# hexapod.net
KiCad netlist of a schematic drawn in EAGLE
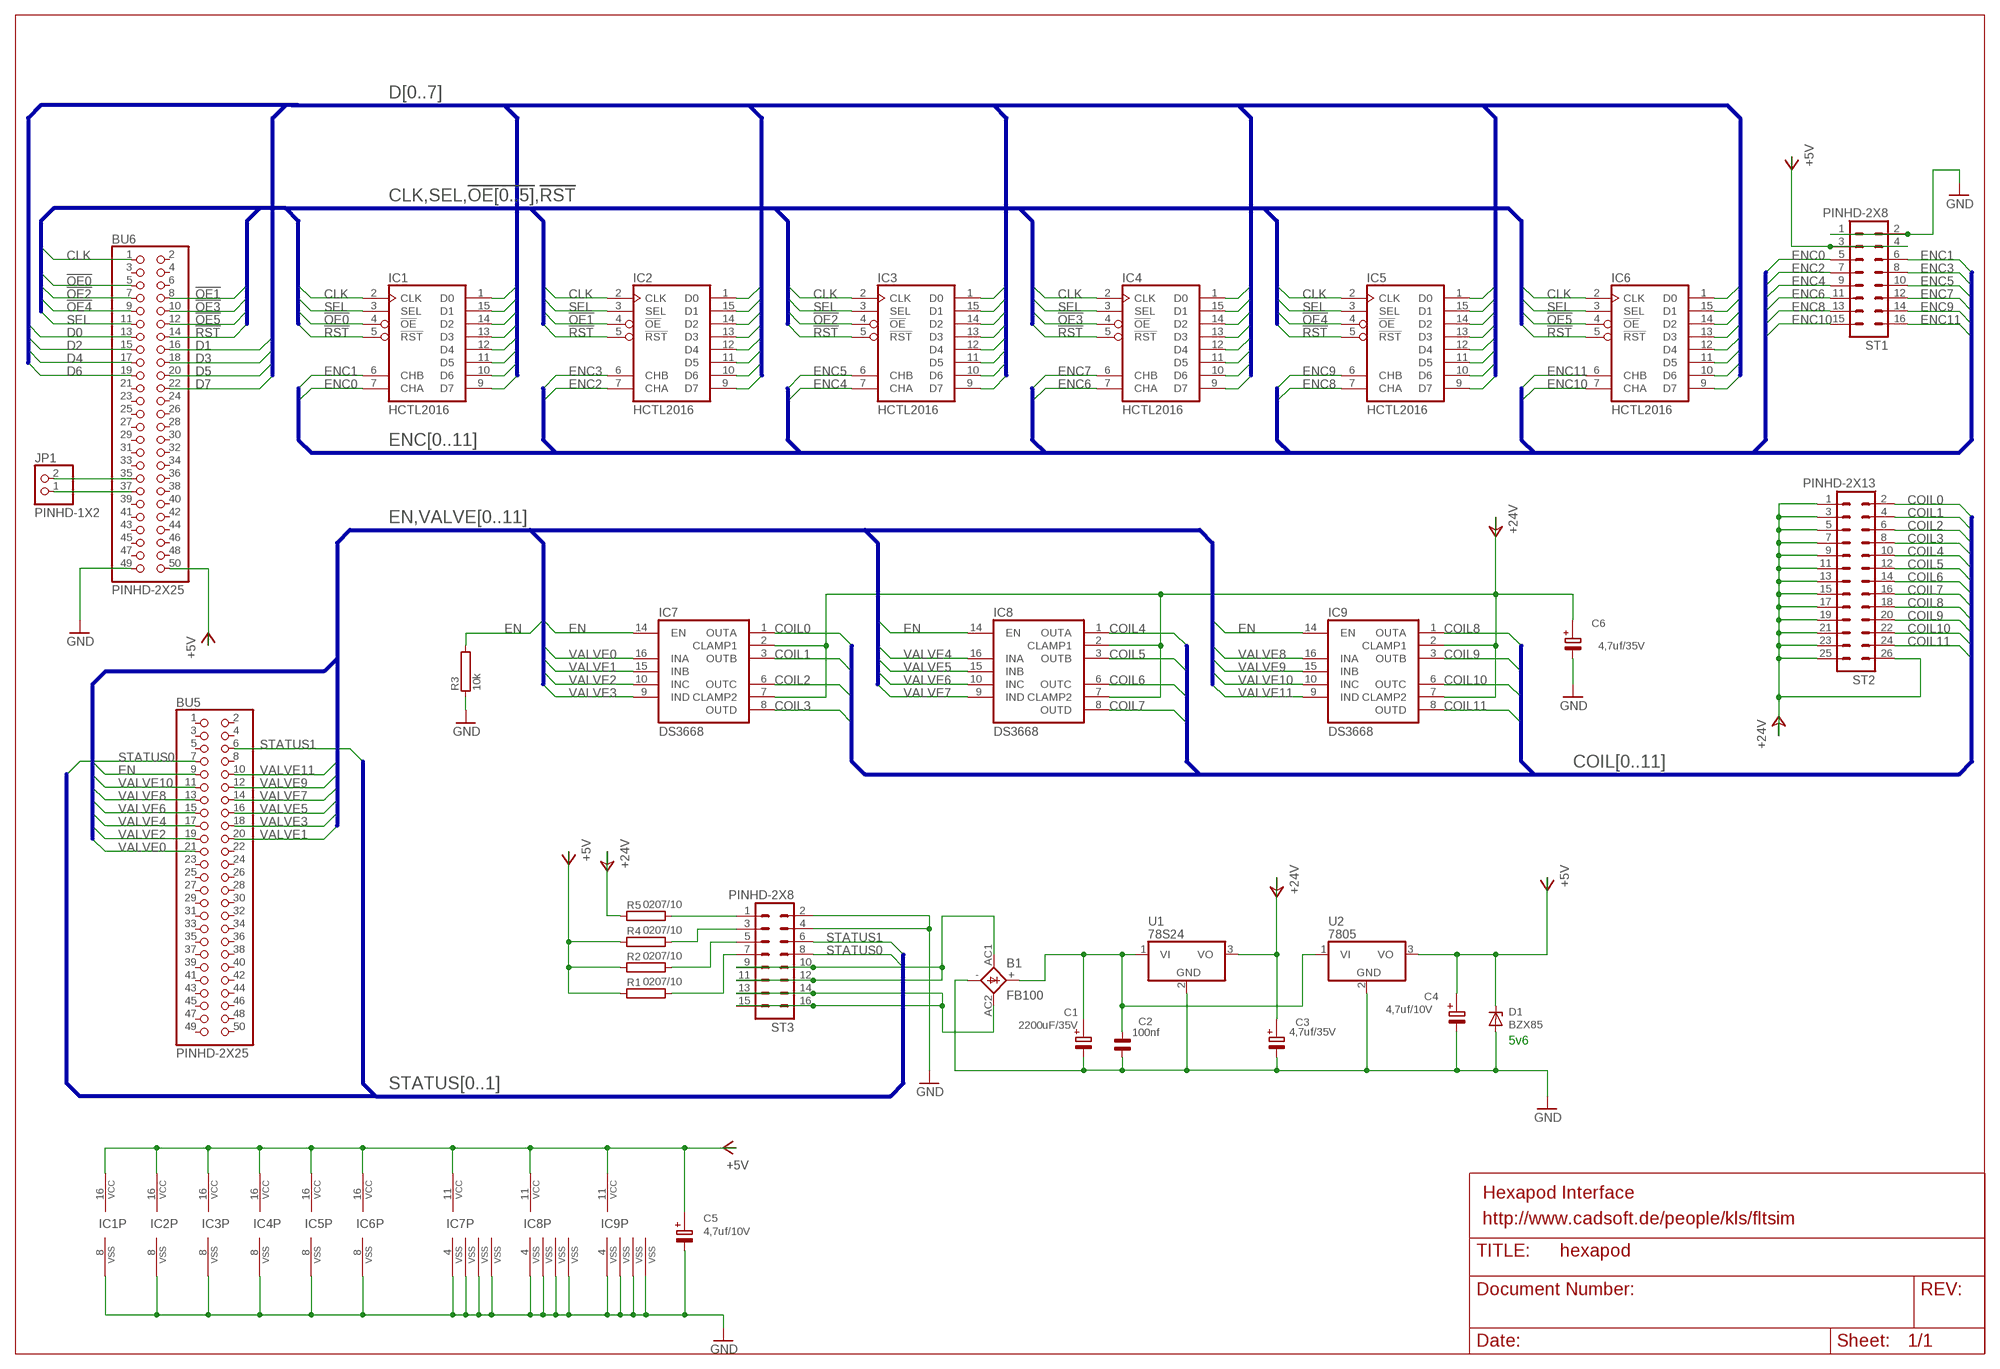
[diagram p0: schematic, sheet 1]

(export (version "E")
  (design (tool "Eeschema 10.0.6"))
  (components
    (comp (ref "B1")
      (value "FB100")
      (footprint "eagle-import:FB100")
      (libsource (lib "eagle-import") (part "FB100"))
    )
    (comp (ref "BU5")
      (value "PINHD-2X25")
      (footprint "eagle-import:2X25")
      (libsource (lib "eagle-import") (part "PINHD-2X25"))
    )
    (comp (ref "BU6")
      (value "PINHD-2X25")
      (footprint "eagle-import:2X25")
      (libsource (lib "eagle-import") (part "PINHD-2X25"))
    )
    (comp (ref "C1")
      (value "2200uF/35V")
      (footprint "eagle-import:E35-16")
      (libsource (lib "eagle-import") (part "E35-16"))
    )
    (comp (ref "C2")
      (value "100nf")
      (footprint "eagle-import:C5B2,5A")
      (libsource (lib "eagle-import") (part "C5B2,5A"))
    )
    (comp (ref "C3")
      (value "4,7uf/35V")
      (footprint "eagle-import:E2,5-5")
      (libsource (lib "eagle-import") (part "E2-5@1"))
    )
    (comp (ref "C4")
      (value "4,7uf/10V")
      (footprint "eagle-import:E2,5-5")
      (libsource (lib "eagle-import") (part "E2,5-5"))
    )
    (comp (ref "C5")
      (value "4,7uf/10V")
      (footprint "eagle-import:E2,5-5")
      (libsource (lib "eagle-import") (part "E2,5-5"))
    )
    (comp (ref "C6")
      (value "4,7uf/35V")
      (footprint "eagle-import:E2,5-5")
      (libsource (lib "eagle-import") (part "E2-5@1"))
    )
    (comp (ref "D1")
      (value "BZX85")
      (footprint "eagle-import:DO41Z10")
      (libsource (lib "eagle-import") (part "BZX85"))
    )
    (comp (ref "IC1")
      (value "HCTL2016")
      (footprint "eagle-import:DIL-16")
      (libsource (lib "eagle-import") (part "HCTL2016"))
    )
    (comp (ref "IC2")
      (value "HCTL2016")
      (footprint "eagle-import:DIL-16")
      (libsource (lib "eagle-import") (part "HCTL2016"))
    )
    (comp (ref "IC3")
      (value "HCTL2016")
      (footprint "eagle-import:DIL-16")
      (libsource (lib "eagle-import") (part "HCTL2016"))
    )
    (comp (ref "IC4")
      (value "HCTL2016")
      (footprint "eagle-import:DIL-16")
      (libsource (lib "eagle-import") (part "HCTL2016"))
    )
    (comp (ref "IC5")
      (value "HCTL2016")
      (footprint "eagle-import:DIL-16")
      (libsource (lib "eagle-import") (part "HCTL2016"))
    )
    (comp (ref "IC6")
      (value "HCTL2016")
      (footprint "eagle-import:DIL-16")
      (libsource (lib "eagle-import") (part "HCTL2016"))
    )
    (comp (ref "IC7")
      (value "DS3668")
      (footprint "eagle-import:DIL-16")
      (libsource (lib "eagle-import") (part "DS3668"))
    )
    (comp (ref "IC8")
      (value "DS3668")
      (footprint "eagle-import:DIL-16")
      (libsource (lib "eagle-import") (part "DS3668"))
    )
    (comp (ref "IC9")
      (value "DS3668")
      (footprint "eagle-import:DIL-16")
      (libsource (lib "eagle-import") (part "DS3668"))
    )
    (comp (ref "JP1")
      (value "PINHD-1X2")
      (footprint "eagle-import:1X02")
      (libsource (lib "eagle-import") (part "PINHD-1X2"))
    )
    (comp (ref "R1")
      (value "0207/10")
      (footprint "eagle-import:0207_10")
      (libsource (lib "eagle-import") (part "0207/10"))
    )
    (comp (ref "R2")
      (value "0207/10")
      (footprint "eagle-import:0207_10")
      (libsource (lib "eagle-import") (part "0207/10"))
    )
    (comp (ref "R3")
      (value "10k")
      (footprint "eagle-import:0207_10")
      (libsource (lib "eagle-import") (part "0207/10"))
    )
    (comp (ref "R4")
      (value "0207/10")
      (footprint "eagle-import:0207_10")
      (libsource (lib "eagle-import") (part "0207/10"))
    )
    (comp (ref "R5")
      (value "0207/10")
      (footprint "eagle-import:0207_10")
      (libsource (lib "eagle-import") (part "0207/10"))
    )
    (comp (ref "ST1")
      (value "PINHD-2X8")
      (footprint "eagle-import:ML16")
      (libsource (lib "eagle-import") (part "ML16"))
    )
    (comp (ref "ST2")
      (value "PINHD-2X13")
      (footprint "eagle-import:ML26")
      (libsource (lib "eagle-import") (part "ML26"))
    )
    (comp (ref "ST3")
      (value "PINHD-2X8")
      (footprint "eagle-import:ML16")
      (libsource (lib "eagle-import") (part "ML16"))
    )
    (comp (ref "U1")
      (value "78S24")
      (footprint "eagle-import:TO220H")
      (libsource (lib "eagle-import") (part "78T24"))
    )
    (comp (ref "U2")
      (value "7805")
      (footprint "eagle-import:TO220H")
      (libsource (lib "eagle-import") (part "78T05"))
    )
  )
  (nets
    (net (code "13") (name "+5V") (class "Default")
      (node (ref "BU6") (pin "50") (pinfunction "50_50") (pintype "passive"))
      (node (ref "C4") (pin "+") (pinfunction "+_+") (pintype "passive"))
      (node (ref "C5") (pin "+") (pinfunction "+_+") (pintype "passive"))
      (node (ref "D1") (pin "C") (pinfunction "C_C") (pintype "passive"))
      (node (ref "IC1") (pin "16") (pinfunction "VCC_16") (pintype "power_in"))
      (node (ref "IC2") (pin "16") (pinfunction "VCC_16") (pintype "power_in"))
      (node (ref "IC3") (pin "16") (pinfunction "VCC_16") (pintype "power_in"))
      (node (ref "IC4") (pin "16") (pinfunction "VCC_16") (pintype "power_in"))
      (node (ref "IC5") (pin "16") (pinfunction "VCC_16") (pintype "power_in"))
      (node (ref "IC6") (pin "16") (pinfunction "VCC_16") (pintype "power_in"))
      (node (ref "IC7") (pin "11") (pinfunction "VCC_11") (pintype "power_in"))
      (node (ref "IC8") (pin "11") (pinfunction "VCC_11") (pintype "power_in"))
      (node (ref "IC9") (pin "11") (pinfunction "VCC_11") (pintype "power_in"))
      (node (ref "R1") (pin "1") (pinfunction "1_1") (pintype "passive"))
      (node (ref "R2") (pin "1") (pinfunction "1_1") (pintype "passive"))
      (node (ref "R4") (pin "1") (pinfunction "1_1") (pintype "passive"))
      (node (ref "ST1") (pin "3") (pinfunction "3_3") (pintype "passive"))
      (node (ref "ST1") (pin "4") (pinfunction "4_4") (pintype "passive"))
      (node (ref "U2") (pin "3") (pinfunction "VO_3") (pintype "passive"))
    )
    (net (code "14") (name "+24V") (class "Default")
      (node (ref "C3") (pin "+") (pinfunction "+_+") (pintype "passive"))
      (node (ref "C6") (pin "+") (pinfunction "+_+") (pintype "passive"))
      (node (ref "IC7") (pin "2") (pinfunction "CLAMP1_2") (pintype "bidirectional"))
      (node (ref "IC7") (pin "7") (pinfunction "CLAMP2_7") (pintype "bidirectional"))
      (node (ref "IC8") (pin "2") (pinfunction "CLAMP1_2") (pintype "bidirectional"))
      (node (ref "IC8") (pin "7") (pinfunction "CLAMP2_7") (pintype "bidirectional"))
      (node (ref "IC9") (pin "2") (pinfunction "CLAMP1_2") (pintype "bidirectional"))
      (node (ref "IC9") (pin "7") (pinfunction "CLAMP2_7") (pintype "bidirectional"))
      (node (ref "R5") (pin "1") (pinfunction "1_1") (pintype "passive"))
      (node (ref "ST2") (pin "1") (pinfunction "1_1") (pintype "passive"))
      (node (ref "ST2") (pin "11") (pinfunction "11_11") (pintype "passive"))
      (node (ref "ST2") (pin "13") (pinfunction "13_13") (pintype "passive"))
      (node (ref "ST2") (pin "15") (pinfunction "15_15") (pintype "passive"))
      (node (ref "ST2") (pin "17") (pinfunction "17_17") (pintype "passive"))
      (node (ref "ST2") (pin "19") (pinfunction "19_19") (pintype "passive"))
      (node (ref "ST2") (pin "21") (pinfunction "21_21") (pintype "passive"))
      (node (ref "ST2") (pin "23") (pinfunction "23_23") (pintype "passive"))
      (node (ref "ST2") (pin "25") (pinfunction "25_25") (pintype "passive"))
      (node (ref "ST2") (pin "26") (pinfunction "26_26") (pintype "passive"))
      (node (ref "ST2") (pin "3") (pinfunction "3_3") (pintype "passive"))
      (node (ref "ST2") (pin "5") (pinfunction "5_5") (pintype "passive"))
      (node (ref "ST2") (pin "7") (pinfunction "7_7") (pintype "passive"))
      (node (ref "ST2") (pin "9") (pinfunction "9_9") (pintype "passive"))
      (node (ref "U1") (pin "3") (pinfunction "VO_3") (pintype "passive"))
    )
    (net (code "15") (name "/CLK") (class "Default")
      (node (ref "BU6") (pin "1") (pinfunction "1_1") (pintype "passive"))
      (node (ref "IC1") (pin "2") (pinfunction "CLK_2") (pintype "input"))
      (node (ref "IC2") (pin "2") (pinfunction "CLK_2") (pintype "input"))
      (node (ref "IC3") (pin "2") (pinfunction "CLK_2") (pintype "input"))
      (node (ref "IC4") (pin "2") (pinfunction "CLK_2") (pintype "input"))
      (node (ref "IC5") (pin "2") (pinfunction "CLK_2") (pintype "input"))
      (node (ref "IC6") (pin "2") (pinfunction "CLK_2") (pintype "input"))
    )
    (net (code "16") (name "/COIL0") (class "Default")
      (node (ref "IC7") (pin "1") (pinfunction "OUTA_1") (pintype "bidirectional"))
      (node (ref "ST2") (pin "2") (pinfunction "2_2") (pintype "passive"))
    )
    (net (code "17") (name "/COIL1") (class "Default")
      (node (ref "IC7") (pin "3") (pinfunction "OUTB_3") (pintype "bidirectional"))
      (node (ref "ST2") (pin "4") (pinfunction "4_4") (pintype "passive"))
    )
    (net (code "18") (name "/COIL2") (class "Default")
      (node (ref "IC7") (pin "6") (pinfunction "OUTC_6") (pintype "bidirectional"))
      (node (ref "ST2") (pin "6") (pinfunction "6_6") (pintype "passive"))
    )
    (net (code "19") (name "/COIL3") (class "Default")
      (node (ref "IC7") (pin "8") (pinfunction "OUTD_8") (pintype "bidirectional"))
      (node (ref "ST2") (pin "8") (pinfunction "8_8") (pintype "passive"))
    )
    (net (code "20") (name "/COIL4") (class "Default")
      (node (ref "IC8") (pin "1") (pinfunction "OUTA_1") (pintype "bidirectional"))
      (node (ref "ST2") (pin "10") (pinfunction "10_10") (pintype "passive"))
    )
    (net (code "21") (name "/COIL5") (class "Default")
      (node (ref "IC8") (pin "3") (pinfunction "OUTB_3") (pintype "bidirectional"))
      (node (ref "ST2") (pin "12") (pinfunction "12_12") (pintype "passive"))
    )
    (net (code "22") (name "/COIL6") (class "Default")
      (node (ref "IC8") (pin "6") (pinfunction "OUTC_6") (pintype "bidirectional"))
      (node (ref "ST2") (pin "14") (pinfunction "14_14") (pintype "passive"))
    )
    (net (code "23") (name "/COIL7") (class "Default")
      (node (ref "IC8") (pin "8") (pinfunction "OUTD_8") (pintype "bidirectional"))
      (node (ref "ST2") (pin "16") (pinfunction "16_16") (pintype "passive"))
    )
    (net (code "24") (name "/COIL8") (class "Default")
      (node (ref "IC9") (pin "1") (pinfunction "OUTA_1") (pintype "bidirectional"))
      (node (ref "ST2") (pin "18") (pinfunction "18_18") (pintype "passive"))
    )
    (net (code "25") (name "/COIL9") (class "Default")
      (node (ref "IC9") (pin "3") (pinfunction "OUTB_3") (pintype "bidirectional"))
      (node (ref "ST2") (pin "20") (pinfunction "20_20") (pintype "passive"))
    )
    (net (code "26") (name "/COIL10") (class "Default")
      (node (ref "IC9") (pin "6") (pinfunction "OUTC_6") (pintype "bidirectional"))
      (node (ref "ST2") (pin "22") (pinfunction "22_22") (pintype "passive"))
    )
    (net (code "27") (name "/COIL11") (class "Default")
      (node (ref "IC9") (pin "8") (pinfunction "OUTD_8") (pintype "bidirectional"))
      (node (ref "ST2") (pin "24") (pinfunction "24_24") (pintype "passive"))
    )
    (net (code "29") (name "/D0") (class "Default")
      (node (ref "BU6") (pin "13") (pinfunction "13_13") (pintype "passive"))
      (node (ref "IC1") (pin "1") (pinfunction "D0_1") (pintype "output"))
      (node (ref "IC2") (pin "1") (pinfunction "D0_1") (pintype "output"))
      (node (ref "IC3") (pin "1") (pinfunction "D0_1") (pintype "output"))
      (node (ref "IC4") (pin "1") (pinfunction "D0_1") (pintype "output"))
      (node (ref "IC5") (pin "1") (pinfunction "D0_1") (pintype "output"))
      (node (ref "IC6") (pin "1") (pinfunction "D0_1") (pintype "output"))
    )
    (net (code "30") (name "/D1") (class "Default")
      (node (ref "BU6") (pin "16") (pinfunction "16_16") (pintype "passive"))
      (node (ref "IC1") (pin "15") (pinfunction "D1_15") (pintype "output"))
      (node (ref "IC2") (pin "15") (pinfunction "D1_15") (pintype "output"))
      (node (ref "IC3") (pin "15") (pinfunction "D1_15") (pintype "output"))
      (node (ref "IC4") (pin "15") (pinfunction "D1_15") (pintype "output"))
      (node (ref "IC5") (pin "15") (pinfunction "D1_15") (pintype "output"))
      (node (ref "IC6") (pin "15") (pinfunction "D1_15") (pintype "output"))
    )
    (net (code "31") (name "/D2") (class "Default")
      (node (ref "BU6") (pin "15") (pinfunction "15_15") (pintype "passive"))
      (node (ref "IC1") (pin "14") (pinfunction "D2_14") (pintype "output"))
      (node (ref "IC2") (pin "14") (pinfunction "D2_14") (pintype "output"))
      (node (ref "IC3") (pin "14") (pinfunction "D2_14") (pintype "output"))
      (node (ref "IC4") (pin "14") (pinfunction "D2_14") (pintype "output"))
      (node (ref "IC5") (pin "14") (pinfunction "D2_14") (pintype "output"))
      (node (ref "IC6") (pin "14") (pinfunction "D2_14") (pintype "output"))
    )
    (net (code "32") (name "/D3") (class "Default")
      (node (ref "BU6") (pin "18") (pinfunction "18_18") (pintype "passive"))
      (node (ref "IC1") (pin "13") (pinfunction "D3_13") (pintype "output"))
      (node (ref "IC2") (pin "13") (pinfunction "D3_13") (pintype "output"))
      (node (ref "IC3") (pin "13") (pinfunction "D3_13") (pintype "output"))
      (node (ref "IC4") (pin "13") (pinfunction "D3_13") (pintype "output"))
      (node (ref "IC5") (pin "13") (pinfunction "D3_13") (pintype "output"))
      (node (ref "IC6") (pin "13") (pinfunction "D3_13") (pintype "output"))
    )
    (net (code "33") (name "/D4") (class "Default")
      (node (ref "BU6") (pin "17") (pinfunction "17_17") (pintype "passive"))
      (node (ref "IC1") (pin "12") (pinfunction "D4_12") (pintype "output"))
      (node (ref "IC2") (pin "12") (pinfunction "D4_12") (pintype "output"))
      (node (ref "IC3") (pin "12") (pinfunction "D4_12") (pintype "output"))
      (node (ref "IC4") (pin "12") (pinfunction "D4_12") (pintype "output"))
      (node (ref "IC5") (pin "12") (pinfunction "D4_12") (pintype "output"))
      (node (ref "IC6") (pin "12") (pinfunction "D4_12") (pintype "output"))
    )
    (net (code "34") (name "/D5") (class "Default")
      (node (ref "BU6") (pin "20") (pinfunction "20_20") (pintype "passive"))
      (node (ref "IC1") (pin "11") (pinfunction "D5_11") (pintype "output"))
      (node (ref "IC2") (pin "11") (pinfunction "D5_11") (pintype "output"))
      (node (ref "IC3") (pin "11") (pinfunction "D5_11") (pintype "output"))
      (node (ref "IC4") (pin "11") (pinfunction "D5_11") (pintype "output"))
      (node (ref "IC5") (pin "11") (pinfunction "D5_11") (pintype "output"))
      (node (ref "IC6") (pin "11") (pinfunction "D5_11") (pintype "output"))
    )
    (net (code "35") (name "/D6") (class "Default")
      (node (ref "BU6") (pin "19") (pinfunction "19_19") (pintype "passive"))
      (node (ref "IC1") (pin "10") (pinfunction "D6_10") (pintype "output"))
      (node (ref "IC2") (pin "10") (pinfunction "D6_10") (pintype "output"))
      (node (ref "IC3") (pin "10") (pinfunction "D6_10") (pintype "output"))
      (node (ref "IC4") (pin "10") (pinfunction "D6_10") (pintype "output"))
      (node (ref "IC5") (pin "10") (pinfunction "D6_10") (pintype "output"))
      (node (ref "IC6") (pin "10") (pinfunction "D6_10") (pintype "output"))
    )
    (net (code "36") (name "/D7") (class "Default")
      (node (ref "BU6") (pin "22") (pinfunction "22_22") (pintype "passive"))
      (node (ref "IC1") (pin "9") (pinfunction "D7_9") (pintype "output"))
      (node (ref "IC2") (pin "9") (pinfunction "D7_9") (pintype "output"))
      (node (ref "IC3") (pin "9") (pinfunction "D7_9") (pintype "output"))
      (node (ref "IC4") (pin "9") (pinfunction "D7_9") (pintype "output"))
      (node (ref "IC5") (pin "9") (pinfunction "D7_9") (pintype "output"))
      (node (ref "IC6") (pin "9") (pinfunction "D7_9") (pintype "output"))
    )
    (net (code "38") (name "/EN") (class "Default")
      (node (ref "BU5") (pin "9") (pinfunction "9_9") (pintype "passive"))
      (node (ref "IC7") (pin "14") (pinfunction "EN_14") (pintype "input"))
      (node (ref "IC8") (pin "14") (pinfunction "EN_14") (pintype "input"))
      (node (ref "IC9") (pin "14") (pinfunction "EN_14") (pintype "input"))
      (node (ref "R3") (pin "2") (pinfunction "2_2") (pintype "passive"))
    )
    (net (code "40") (name "/ENC0") (class "Default")
      (node (ref "IC1") (pin "7") (pinfunction "CHA_7") (pintype "input"))
      (node (ref "ST1") (pin "5") (pinfunction "5_5") (pintype "passive"))
    )
    (net (code "41") (name "/ENC1") (class "Default")
      (node (ref "IC1") (pin "6") (pinfunction "CHB_6") (pintype "input"))
      (node (ref "ST1") (pin "6") (pinfunction "6_6") (pintype "passive"))
    )
    (net (code "42") (name "/ENC2") (class "Default")
      (node (ref "IC2") (pin "7") (pinfunction "CHA_7") (pintype "input"))
      (node (ref "ST1") (pin "7") (pinfunction "7_7") (pintype "passive"))
    )
    (net (code "43") (name "/ENC3") (class "Default")
      (node (ref "IC2") (pin "6") (pinfunction "CHB_6") (pintype "input"))
      (node (ref "ST1") (pin "8") (pinfunction "8_8") (pintype "passive"))
    )
    (net (code "44") (name "/ENC4") (class "Default")
      (node (ref "IC3") (pin "7") (pinfunction "CHA_7") (pintype "input"))
      (node (ref "ST1") (pin "9") (pinfunction "9_9") (pintype "passive"))
    )
    (net (code "45") (name "/ENC5") (class "Default")
      (node (ref "IC3") (pin "6") (pinfunction "CHB_6") (pintype "input"))
      (node (ref "ST1") (pin "10") (pinfunction "10_10") (pintype "passive"))
    )
    (net (code "46") (name "/ENC6") (class "Default")
      (node (ref "IC4") (pin "7") (pinfunction "CHA_7") (pintype "input"))
      (node (ref "ST1") (pin "11") (pinfunction "11_11") (pintype "passive"))
    )
    (net (code "47") (name "/ENC7") (class "Default")
      (node (ref "IC4") (pin "6") (pinfunction "CHB_6") (pintype "input"))
      (node (ref "ST1") (pin "12") (pinfunction "12_12") (pintype "passive"))
    )
    (net (code "48") (name "/ENC8") (class "Default")
      (node (ref "IC5") (pin "7") (pinfunction "CHA_7") (pintype "input"))
      (node (ref "ST1") (pin "13") (pinfunction "13_13") (pintype "passive"))
    )
    (net (code "49") (name "/ENC9") (class "Default")
      (node (ref "IC5") (pin "6") (pinfunction "CHB_6") (pintype "input"))
      (node (ref "ST1") (pin "14") (pinfunction "14_14") (pintype "passive"))
    )
    (net (code "50") (name "/ENC10") (class "Default")
      (node (ref "IC6") (pin "7") (pinfunction "CHA_7") (pintype "input"))
      (node (ref "ST1") (pin "15") (pinfunction "15_15") (pintype "passive"))
    )
    (net (code "51") (name "/ENC11") (class "Default")
      (node (ref "IC6") (pin "6") (pinfunction "CHB_6") (pintype "input"))
      (node (ref "ST1") (pin "16") (pinfunction "16_16") (pintype "passive"))
    )
    (net (code "53") (name "/SEL") (class "Default")
      (node (ref "BU6") (pin "11") (pinfunction "11_11") (pintype "passive"))
      (node (ref "IC1") (pin "3") (pinfunction "SEL_3") (pintype "input"))
      (node (ref "IC2") (pin "3") (pinfunction "SEL_3") (pintype "input"))
      (node (ref "IC3") (pin "3") (pinfunction "SEL_3") (pintype "input"))
      (node (ref "IC4") (pin "3") (pinfunction "SEL_3") (pintype "input"))
      (node (ref "IC5") (pin "3") (pinfunction "SEL_3") (pintype "input"))
      (node (ref "IC6") (pin "3") (pinfunction "SEL_3") (pintype "input"))
    )
    (net (code "54") (name "/STATUS0") (class "Default")
      (node (ref "BU5") (pin "7") (pinfunction "7_7") (pintype "passive"))
      (node (ref "ST3") (pin "8") (pinfunction "8_8") (pintype "passive"))
    )
    (net (code "55") (name "/STATUS1") (class "Default")
      (node (ref "BU5") (pin "6") (pinfunction "6_6") (pintype "passive"))
      (node (ref "ST3") (pin "6") (pinfunction "6_6") (pintype "passive"))
    )
    (net (code "57") (name "/VALVE0") (class "Default")
      (node (ref "BU5") (pin "21") (pinfunction "21_21") (pintype "passive"))
      (node (ref "IC7") (pin "16") (pinfunction "INA_16") (pintype "input"))
    )
    (net (code "58") (name "/VALVE1") (class "Default")
      (node (ref "BU5") (pin "20") (pinfunction "20_20") (pintype "passive"))
      (node (ref "IC7") (pin "15") (pinfunction "INB_15") (pintype "input"))
    )
    (net (code "59") (name "/VALVE2") (class "Default")
      (node (ref "BU5") (pin "19") (pinfunction "19_19") (pintype "passive"))
      (node (ref "IC7") (pin "10") (pinfunction "INC_10") (pintype "input"))
    )
    (net (code "60") (name "/VALVE3") (class "Default")
      (node (ref "BU5") (pin "18") (pinfunction "18_18") (pintype "passive"))
      (node (ref "IC7") (pin "9") (pinfunction "IND_9") (pintype "input"))
    )
    (net (code "61") (name "/VALVE4") (class "Default")
      (node (ref "BU5") (pin "17") (pinfunction "17_17") (pintype "passive"))
      (node (ref "IC8") (pin "16") (pinfunction "INA_16") (pintype "input"))
    )
    (net (code "62") (name "/VALVE5") (class "Default")
      (node (ref "BU5") (pin "16") (pinfunction "16_16") (pintype "passive"))
      (node (ref "IC8") (pin "15") (pinfunction "INB_15") (pintype "input"))
    )
    (net (code "63") (name "/VALVE6") (class "Default")
      (node (ref "BU5") (pin "15") (pinfunction "15_15") (pintype "passive"))
      (node (ref "IC8") (pin "10") (pinfunction "INC_10") (pintype "input"))
    )
    (net (code "64") (name "/VALVE7") (class "Default")
      (node (ref "BU5") (pin "14") (pinfunction "14_14") (pintype "passive"))
      (node (ref "IC8") (pin "9") (pinfunction "IND_9") (pintype "input"))
    )
    (net (code "65") (name "/VALVE8") (class "Default")
      (node (ref "BU5") (pin "13") (pinfunction "13_13") (pintype "passive"))
      (node (ref "IC9") (pin "16") (pinfunction "INA_16") (pintype "input"))
    )
    (net (code "66") (name "/VALVE9") (class "Default")
      (node (ref "BU5") (pin "12") (pinfunction "12_12") (pintype "passive"))
      (node (ref "IC9") (pin "15") (pinfunction "INB_15") (pintype "input"))
    )
    (net (code "67") (name "/VALVE10") (class "Default")
      (node (ref "BU5") (pin "11") (pinfunction "11_11") (pintype "passive"))
      (node (ref "IC9") (pin "10") (pinfunction "INC_10") (pintype "input"))
    )
    (net (code "68") (name "/VALVE11") (class "Default")
      (node (ref "BU5") (pin "10") (pinfunction "10_10") (pintype "passive"))
      (node (ref "IC9") (pin "9") (pinfunction "IND_9") (pintype "input"))
    )
    (net (code "70") (name "/~{OE0}") (class "Default")
      (node (ref "BU6") (pin "5") (pinfunction "5_5") (pintype "passive"))
      (node (ref "IC1") (pin "4") (pinfunction "~{OE}_4") (pintype "input"))
    )
    (net (code "71") (name "/~{OE1}") (class "Default")
      (node (ref "BU6") (pin "8") (pinfunction "8_8") (pintype "passive"))
      (node (ref "IC2") (pin "4") (pinfunction "~{OE}_4") (pintype "input"))
    )
    (net (code "72") (name "/~{OE2}") (class "Default")
      (node (ref "BU6") (pin "7") (pinfunction "7_7") (pintype "passive"))
      (node (ref "IC3") (pin "4") (pinfunction "~{OE}_4") (pintype "input"))
    )
    (net (code "73") (name "/~{OE3}") (class "Default")
      (node (ref "BU6") (pin "10") (pinfunction "10_10") (pintype "passive"))
      (node (ref "IC4") (pin "4") (pinfunction "~{OE}_4") (pintype "input"))
    )
    (net (code "74") (name "/~{OE4}") (class "Default")
      (node (ref "BU6") (pin "9") (pinfunction "9_9") (pintype "passive"))
      (node (ref "IC5") (pin "4") (pinfunction "~{OE}_4") (pintype "input"))
    )
    (net (code "75") (name "/~{OE5}") (class "Default")
      (node (ref "BU6") (pin "12") (pinfunction "12_12") (pintype "passive"))
      (node (ref "IC6") (pin "4") (pinfunction "~{OE}_4") (pintype "input"))
    )
    (net (code "76") (name "/~{RST}") (class "Default")
      (node (ref "BU6") (pin "14") (pinfunction "14_14") (pintype "passive"))
      (node (ref "IC1") (pin "5") (pinfunction "~{RST}_5") (pintype "input"))
      (node (ref "IC2") (pin "5") (pinfunction "~{RST}_5") (pintype "input"))
      (node (ref "IC3") (pin "5") (pinfunction "~{RST}_5") (pintype "input"))
      (node (ref "IC4") (pin "5") (pinfunction "~{RST}_5") (pintype "input"))
      (node (ref "IC5") (pin "5") (pinfunction "~{RST}_5") (pintype "input"))
      (node (ref "IC6") (pin "5") (pinfunction "~{RST}_5") (pintype "input"))
    )
    (net (code "77") (name "GND") (class "Default")
      (node (ref "B1") (pin "-") (pinfunction "-_-") (pintype "passive"))
      (node (ref "BU6") (pin "49") (pinfunction "49_49") (pintype "passive"))
      (node (ref "C1") (pin "-") (pinfunction "-_-") (pintype "passive"))
      (node (ref "C2") (pin "1") (pinfunction "1_1") (pintype "passive"))
      (node (ref "C3") (pin "-") (pinfunction "-_-") (pintype "passive"))
      (node (ref "C4") (pin "-") (pinfunction "-_-") (pintype "passive"))
      (node (ref "C5") (pin "-") (pinfunction "-_-") (pintype "passive"))
      (node (ref "C6") (pin "-") (pinfunction "-_-") (pintype "passive"))
      (node (ref "D1") (pin "A") (pinfunction "A_A") (pintype "passive"))
      (node (ref "IC1") (pin "8") (pinfunction "VSS_8") (pintype "power_in"))
      (node (ref "IC2") (pin "8") (pinfunction "VSS_8") (pintype "power_in"))
      (node (ref "IC3") (pin "8") (pinfunction "VSS_8") (pintype "power_in"))
      (node (ref "IC4") (pin "8") (pinfunction "VSS_8") (pintype "power_in"))
      (node (ref "IC5") (pin "8") (pinfunction "VSS_8") (pintype "power_in"))
      (node (ref "IC6") (pin "8") (pinfunction "VSS_8") (pintype "power_in"))
      (node (ref "IC7") (pin "12") (pinfunction "VSS_12") (pintype "power_in"))
      (node (ref "IC7") (pin "13") (pinfunction "VSS_13") (pintype "power_in"))
      (node (ref "IC7") (pin "4") (pinfunction "VSS_4") (pintype "power_in"))
      (node (ref "IC7") (pin "5") (pinfunction "VSS_5") (pintype "power_in"))
      (node (ref "IC8") (pin "12") (pinfunction "VSS_12") (pintype "power_in"))
      (node (ref "IC8") (pin "13") (pinfunction "VSS_13") (pintype "power_in"))
      (node (ref "IC8") (pin "4") (pinfunction "VSS_4") (pintype "power_in"))
      (node (ref "IC8") (pin "5") (pinfunction "VSS_5") (pintype "power_in"))
      (node (ref "IC9") (pin "12") (pinfunction "VSS_12") (pintype "power_in"))
      (node (ref "IC9") (pin "13") (pinfunction "VSS_13") (pintype "power_in"))
      (node (ref "IC9") (pin "4") (pinfunction "VSS_4") (pintype "power_in"))
      (node (ref "IC9") (pin "5") (pinfunction "VSS_5") (pintype "power_in"))
      (node (ref "R3") (pin "1") (pinfunction "1_1") (pintype "passive"))
      (node (ref "ST1") (pin "1") (pinfunction "1_1") (pintype "passive"))
      (node (ref "ST1") (pin "2") (pinfunction "2_2") (pintype "passive"))
      (node (ref "ST3") (pin "2") (pinfunction "2_2") (pintype "passive"))
      (node (ref "ST3") (pin "4") (pinfunction "4_4") (pintype "passive"))
      (node (ref "U1") (pin "2") (pinfunction "GND_2") (pintype "passive"))
      (node (ref "U2") (pin "2") (pinfunction "GND_2") (pintype "passive"))
    )
    (net (code "78") (name "Net-(B1-PadAC1)") (class "Default")
      (node (ref "B1") (pin "AC1") (pinfunction "AC1_AC1") (pintype "passive"))
      (node (ref "ST3") (pin "10") (pinfunction "10_10") (pintype "passive"))
      (node (ref "ST3") (pin "11") (pinfunction "11_11") (pintype "passive"))
      (node (ref "ST3") (pin "12") (pinfunction "12_12") (pintype "passive"))
      (node (ref "ST3") (pin "9") (pinfunction "9_9") (pintype "passive"))
    )
    (net (code "79") (name "Net-(B1-PadAC2)") (class "Default")
      (node (ref "B1") (pin "AC2") (pinfunction "AC2_AC2") (pintype "passive"))
      (node (ref "ST3") (pin "13") (pinfunction "13_13") (pintype "passive"))
      (node (ref "ST3") (pin "14") (pinfunction "14_14") (pintype "passive"))
      (node (ref "ST3") (pin "15") (pinfunction "15_15") (pintype "passive"))
      (node (ref "ST3") (pin "16") (pinfunction "16_16") (pintype "passive"))
    )
    (net (code "80") (name "Net-(BU6-Pad35)") (class "Default")
      (node (ref "BU6") (pin "35") (pinfunction "35_35") (pintype "passive"))
      (node (ref "JP1") (pin "2") (pinfunction "2_2") (pintype "passive"))
    )
    (net (code "81") (name "Net-(BU6-Pad37)") (class "Default")
      (node (ref "BU6") (pin "37") (pinfunction "37_37") (pintype "passive"))
      (node (ref "JP1") (pin "1") (pinfunction "1_1") (pintype "passive"))
    )
    (net (code "82") (name "Net-(R1-Pad2)") (class "Default")
      (node (ref "R1") (pin "2") (pinfunction "2_2") (pintype "passive"))
      (node (ref "ST3") (pin "7") (pinfunction "7_7") (pintype "passive"))
    )
    (net (code "83") (name "Net-(R2-Pad2)") (class "Default")
      (node (ref "R2") (pin "2") (pinfunction "2_2") (pintype "passive"))
      (node (ref "ST3") (pin "5") (pinfunction "5_5") (pintype "passive"))
    )
    (net (code "84") (name "Net-(R4-Pad2)") (class "Default")
      (node (ref "R4") (pin "2") (pinfunction "2_2") (pintype "passive"))
      (node (ref "ST3") (pin "3") (pinfunction "3_3") (pintype "passive"))
    )
    (net (code "85") (name "Net-(R5-Pad2)") (class "Default")
      (node (ref "R5") (pin "2") (pinfunction "2_2") (pintype "passive"))
      (node (ref "ST3") (pin "1") (pinfunction "1_1") (pintype "passive"))
    )
    (net (code "86") (name "Net-(U1-VI)") (class "Default")
      (node (ref "B1") (pin "+") (pinfunction "+_+") (pintype "passive"))
      (node (ref "C1") (pin "+") (pinfunction "+_+") (pintype "passive"))
      (node (ref "C2") (pin "2") (pinfunction "2_2") (pintype "passive"))
      (node (ref "U1") (pin "1") (pinfunction "VI_1") (pintype "input"))
      (node (ref "U2") (pin "1") (pinfunction "VI_1") (pintype "input"))
    )
    (net (code "87") (name "unconnected-(BU5-Pad1)") (class "Default")
      (node (ref "BU5") (pin "1") (pinfunction "1_1") (pintype "passive"))
    )
    (net (code "88") (name "unconnected-(BU5-Pad2)") (class "Default")
      (node (ref "BU5") (pin "2") (pinfunction "2_2") (pintype "passive"))
    )
    (net (code "89") (name "unconnected-(BU5-Pad3)") (class "Default")
      (node (ref "BU5") (pin "3") (pinfunction "3_3") (pintype "passive"))
    )
    (net (code "90") (name "unconnected-(BU5-Pad4)") (class "Default")
      (node (ref "BU5") (pin "4") (pinfunction "4_4") (pintype "passive"))
    )
    (net (code "91") (name "unconnected-(BU5-Pad5)") (class "Default")
      (node (ref "BU5") (pin "5") (pinfunction "5_5") (pintype "passive"))
    )
    (net (code "92") (name "unconnected-(BU5-Pad8)") (class "Default")
      (node (ref "BU5") (pin "8") (pinfunction "8_8") (pintype "passive"))
    )
    (net (code "93") (name "unconnected-(BU5-Pad22)") (class "Default")
      (node (ref "BU5") (pin "22") (pinfunction "22_22") (pintype "passive"))
    )
    (net (code "94") (name "unconnected-(BU5-Pad23)") (class "Default")
      (node (ref "BU5") (pin "23") (pinfunction "23_23") (pintype "passive"))
    )
    (net (code "95") (name "unconnected-(BU5-Pad24)") (class "Default")
      (node (ref "BU5") (pin "24") (pinfunction "24_24") (pintype "passive"))
    )
    (net (code "96") (name "unconnected-(BU5-Pad25)") (class "Default")
      (node (ref "BU5") (pin "25") (pinfunction "25_25") (pintype "passive"))
    )
    (net (code "97") (name "unconnected-(BU5-Pad26)") (class "Default")
      (node (ref "BU5") (pin "26") (pinfunction "26_26") (pintype "passive"))
    )
    (net (code "98") (name "unconnected-(BU5-Pad27)") (class "Default")
      (node (ref "BU5") (pin "27") (pinfunction "27_27") (pintype "passive"))
    )
    (net (code "99") (name "unconnected-(BU5-Pad28)") (class "Default")
      (node (ref "BU5") (pin "28") (pinfunction "28_28") (pintype "passive"))
    )
    (net (code "100") (name "unconnected-(BU5-Pad29)") (class "Default")
      (node (ref "BU5") (pin "29") (pinfunction "29_29") (pintype "passive"))
    )
    (net (code "101") (name "unconnected-(BU5-Pad30)") (class "Default")
      (node (ref "BU5") (pin "30") (pinfunction "30_30") (pintype "passive"))
    )
    (net (code "102") (name "unconnected-(BU5-Pad31)") (class "Default")
      (node (ref "BU5") (pin "31") (pinfunction "31_31") (pintype "passive"))
    )
    (net (code "103") (name "unconnected-(BU5-Pad32)") (class "Default")
      (node (ref "BU5") (pin "32") (pinfunction "32_32") (pintype "passive"))
    )
    (net (code "104") (name "unconnected-(BU5-Pad33)") (class "Default")
      (node (ref "BU5") (pin "33") (pinfunction "33_33") (pintype "passive"))
    )
    (net (code "105") (name "unconnected-(BU5-Pad34)") (class "Default")
      (node (ref "BU5") (pin "34") (pinfunction "34_34") (pintype "passive"))
    )
    (net (code "106") (name "unconnected-(BU5-Pad35)") (class "Default")
      (node (ref "BU5") (pin "35") (pinfunction "35_35") (pintype "passive"))
    )
    (net (code "107") (name "unconnected-(BU5-Pad36)") (class "Default")
      (node (ref "BU5") (pin "36") (pinfunction "36_36") (pintype "passive"))
    )
    (net (code "108") (name "unconnected-(BU5-Pad37)") (class "Default")
      (node (ref "BU5") (pin "37") (pinfunction "37_37") (pintype "passive"))
    )
    (net (code "109") (name "unconnected-(BU5-Pad38)") (class "Default")
      (node (ref "BU5") (pin "38") (pinfunction "38_38") (pintype "passive"))
    )
    (net (code "110") (name "unconnected-(BU5-Pad39)") (class "Default")
      (node (ref "BU5") (pin "39") (pinfunction "39_39") (pintype "passive"))
    )
    (net (code "111") (name "unconnected-(BU5-Pad40)") (class "Default")
      (node (ref "BU5") (pin "40") (pinfunction "40_40") (pintype "passive"))
    )
    (net (code "112") (name "unconnected-(BU5-Pad41)") (class "Default")
      (node (ref "BU5") (pin "41") (pinfunction "41_41") (pintype "passive"))
    )
    (net (code "113") (name "unconnected-(BU5-Pad42)") (class "Default")
      (node (ref "BU5") (pin "42") (pinfunction "42_42") (pintype "passive"))
    )
    (net (code "114") (name "unconnected-(BU5-Pad43)") (class "Default")
      (node (ref "BU5") (pin "43") (pinfunction "43_43") (pintype "passive"))
    )
    (net (code "115") (name "unconnected-(BU5-Pad44)") (class "Default")
      (node (ref "BU5") (pin "44") (pinfunction "44_44") (pintype "passive"))
    )
    (net (code "116") (name "unconnected-(BU5-Pad45)") (class "Default")
      (node (ref "BU5") (pin "45") (pinfunction "45_45") (pintype "passive"))
    )
    (net (code "117") (name "unconnected-(BU5-Pad46)") (class "Default")
      (node (ref "BU5") (pin "46") (pinfunction "46_46") (pintype "passive"))
    )
    (net (code "118") (name "unconnected-(BU5-Pad47)") (class "Default")
      (node (ref "BU5") (pin "47") (pinfunction "47_47") (pintype "passive"))
    )
    (net (code "119") (name "unconnected-(BU5-Pad48)") (class "Default")
      (node (ref "BU5") (pin "48") (pinfunction "48_48") (pintype "passive"))
    )
    (net (code "120") (name "unconnected-(BU5-Pad49)") (class "Default")
      (node (ref "BU5") (pin "49") (pinfunction "49_49") (pintype "passive"))
    )
    (net (code "121") (name "unconnected-(BU5-Pad50)") (class "Default")
      (node (ref "BU5") (pin "50") (pinfunction "50_50") (pintype "passive"))
    )
    (net (code "122") (name "unconnected-(BU6-Pad2)") (class "Default")
      (node (ref "BU6") (pin "2") (pinfunction "2_2") (pintype "passive"))
    )
    (net (code "123") (name "unconnected-(BU6-Pad3)") (class "Default")
      (node (ref "BU6") (pin "3") (pinfunction "3_3") (pintype "passive"))
    )
    (net (code "124") (name "unconnected-(BU6-Pad4)") (class "Default")
      (node (ref "BU6") (pin "4") (pinfunction "4_4") (pintype "passive"))
    )
    (net (code "125") (name "unconnected-(BU6-Pad6)") (class "Default")
      (node (ref "BU6") (pin "6") (pinfunction "6_6") (pintype "passive"))
    )
    (net (code "126") (name "unconnected-(BU6-Pad21)") (class "Default")
      (node (ref "BU6") (pin "21") (pinfunction "21_21") (pintype "passive"))
    )
    (net (code "127") (name "unconnected-(BU6-Pad23)") (class "Default")
      (node (ref "BU6") (pin "23") (pinfunction "23_23") (pintype "passive"))
    )
    (net (code "128") (name "unconnected-(BU6-Pad24)") (class "Default")
      (node (ref "BU6") (pin "24") (pinfunction "24_24") (pintype "passive"))
    )
    (net (code "129") (name "unconnected-(BU6-Pad25)") (class "Default")
      (node (ref "BU6") (pin "25") (pinfunction "25_25") (pintype "passive"))
    )
    (net (code "130") (name "unconnected-(BU6-Pad26)") (class "Default")
      (node (ref "BU6") (pin "26") (pinfunction "26_26") (pintype "passive"))
    )
    (net (code "131") (name "unconnected-(BU6-Pad27)") (class "Default")
      (node (ref "BU6") (pin "27") (pinfunction "27_27") (pintype "passive"))
    )
    (net (code "132") (name "unconnected-(BU6-Pad28)") (class "Default")
      (node (ref "BU6") (pin "28") (pinfunction "28_28") (pintype "passive"))
    )
    (net (code "133") (name "unconnected-(BU6-Pad29)") (class "Default")
      (node (ref "BU6") (pin "29") (pinfunction "29_29") (pintype "passive"))
    )
    (net (code "134") (name "unconnected-(BU6-Pad30)") (class "Default")
      (node (ref "BU6") (pin "30") (pinfunction "30_30") (pintype "passive"))
    )
    (net (code "135") (name "unconnected-(BU6-Pad31)") (class "Default")
      (node (ref "BU6") (pin "31") (pinfunction "31_31") (pintype "passive"))
    )
    (net (code "136") (name "unconnected-(BU6-Pad32)") (class "Default")
      (node (ref "BU6") (pin "32") (pinfunction "32_32") (pintype "passive"))
    )
    (net (code "137") (name "unconnected-(BU6-Pad33)") (class "Default")
      (node (ref "BU6") (pin "33") (pinfunction "33_33") (pintype "passive"))
    )
    (net (code "138") (name "unconnected-(BU6-Pad34)") (class "Default")
      (node (ref "BU6") (pin "34") (pinfunction "34_34") (pintype "passive"))
    )
    (net (code "139") (name "unconnected-(BU6-Pad36)") (class "Default")
      (node (ref "BU6") (pin "36") (pinfunction "36_36") (pintype "passive"))
    )
    (net (code "140") (name "unconnected-(BU6-Pad38)") (class "Default")
      (node (ref "BU6") (pin "38") (pinfunction "38_38") (pintype "passive"))
    )
    (net (code "141") (name "unconnected-(BU6-Pad39)") (class "Default")
      (node (ref "BU6") (pin "39") (pinfunction "39_39") (pintype "passive"))
    )
    (net (code "142") (name "unconnected-(BU6-Pad40)") (class "Default")
      (node (ref "BU6") (pin "40") (pinfunction "40_40") (pintype "passive"))
    )
    (net (code "143") (name "unconnected-(BU6-Pad41)") (class "Default")
      (node (ref "BU6") (pin "41") (pinfunction "41_41") (pintype "passive"))
    )
    (net (code "144") (name "unconnected-(BU6-Pad42)") (class "Default")
      (node (ref "BU6") (pin "42") (pinfunction "42_42") (pintype "passive"))
    )
    (net (code "145") (name "unconnected-(BU6-Pad43)") (class "Default")
      (node (ref "BU6") (pin "43") (pinfunction "43_43") (pintype "passive"))
    )
    (net (code "146") (name "unconnected-(BU6-Pad44)") (class "Default")
      (node (ref "BU6") (pin "44") (pinfunction "44_44") (pintype "passive"))
    )
    (net (code "147") (name "unconnected-(BU6-Pad45)") (class "Default")
      (node (ref "BU6") (pin "45") (pinfunction "45_45") (pintype "passive"))
    )
    (net (code "148") (name "unconnected-(BU6-Pad46)") (class "Default")
      (node (ref "BU6") (pin "46") (pinfunction "46_46") (pintype "passive"))
    )
    (net (code "149") (name "unconnected-(BU6-Pad47)") (class "Default")
      (node (ref "BU6") (pin "47") (pinfunction "47_47") (pintype "passive"))
    )
    (net (code "150") (name "unconnected-(BU6-Pad48)") (class "Default")
      (node (ref "BU6") (pin "48") (pinfunction "48_48") (pintype "passive"))
    )
  )
)
